# QCopterFC_KEY_Sch.net
KiCad netlist of a schematic drawn in Altium Designer
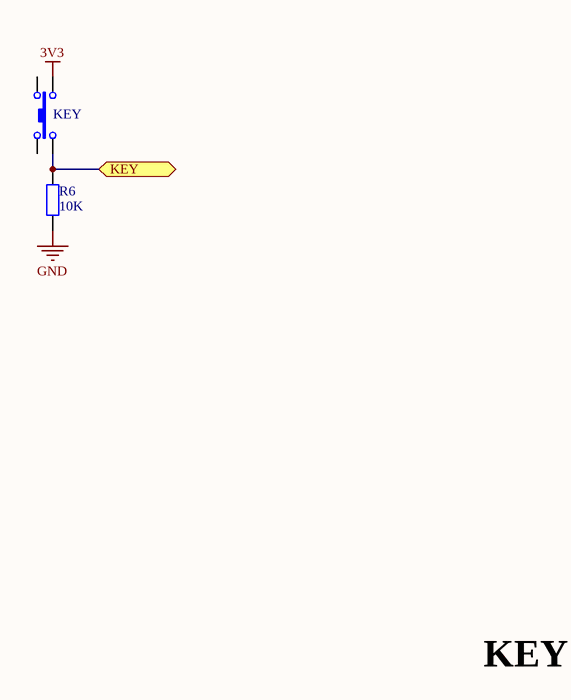
[diagram p0: QCopterFC_KEY_Sch.SchDoc]

(export (version "E")
  (design (tool "Eeschema 10.0.6"))
  (components
    (comp (ref "KEY")
      (value "BT_TACT_4.2x6.4_90")
      (footprint "PCB_Switch:BT_TACT_4.2x6.4_90")
      (description "Switch")
      (libsource (lib "SCH_Switch") (part "BT_TACT_4.2x6.4_90"))
    )
    (comp (ref "R6")
      (value "10K")
      (footprint "PCB_Passive:RES_0603")
      (description "Resistor")
      (fields (field (name "Comment") "Res_0603"))
      (libsource (lib "SCH_Passive") (part "Res_0603"))
    )
  )
  (nets
    (net (code "1") (name "/KEY") (class "Default")
      (node (ref "KEY") (pin "3") (pinfunction "3_3") (pintype "passive"))
      (node (ref "R6") (pin "2") (pinfunction "2_2") (pintype "passive"))
    )
    (net (code "2") (name "3V3") (class "Default")
      (node (ref "KEY") (pin "4") (pinfunction "4_4") (pintype "passive"))
    )
    (net (code "3") (name "GND") (class "Default")
      (node (ref "R6") (pin "1") (pinfunction "1_1") (pintype "passive"))
    )
    (net (code "4") (name "unconnected-(KEY-Pad1)") (class "Default")
      (node (ref "KEY") (pin "1") (pinfunction "1_1") (pintype "passive"))
    )
    (net (code "5") (name "unconnected-(KEY-Pad2)") (class "Default")
      (node (ref "KEY") (pin "2") (pinfunction "2_2") (pintype "passive"))
    )
  )
)
